# vilnius_rev_c.net
KiCad netlist of a schematic drawn in EAGLE
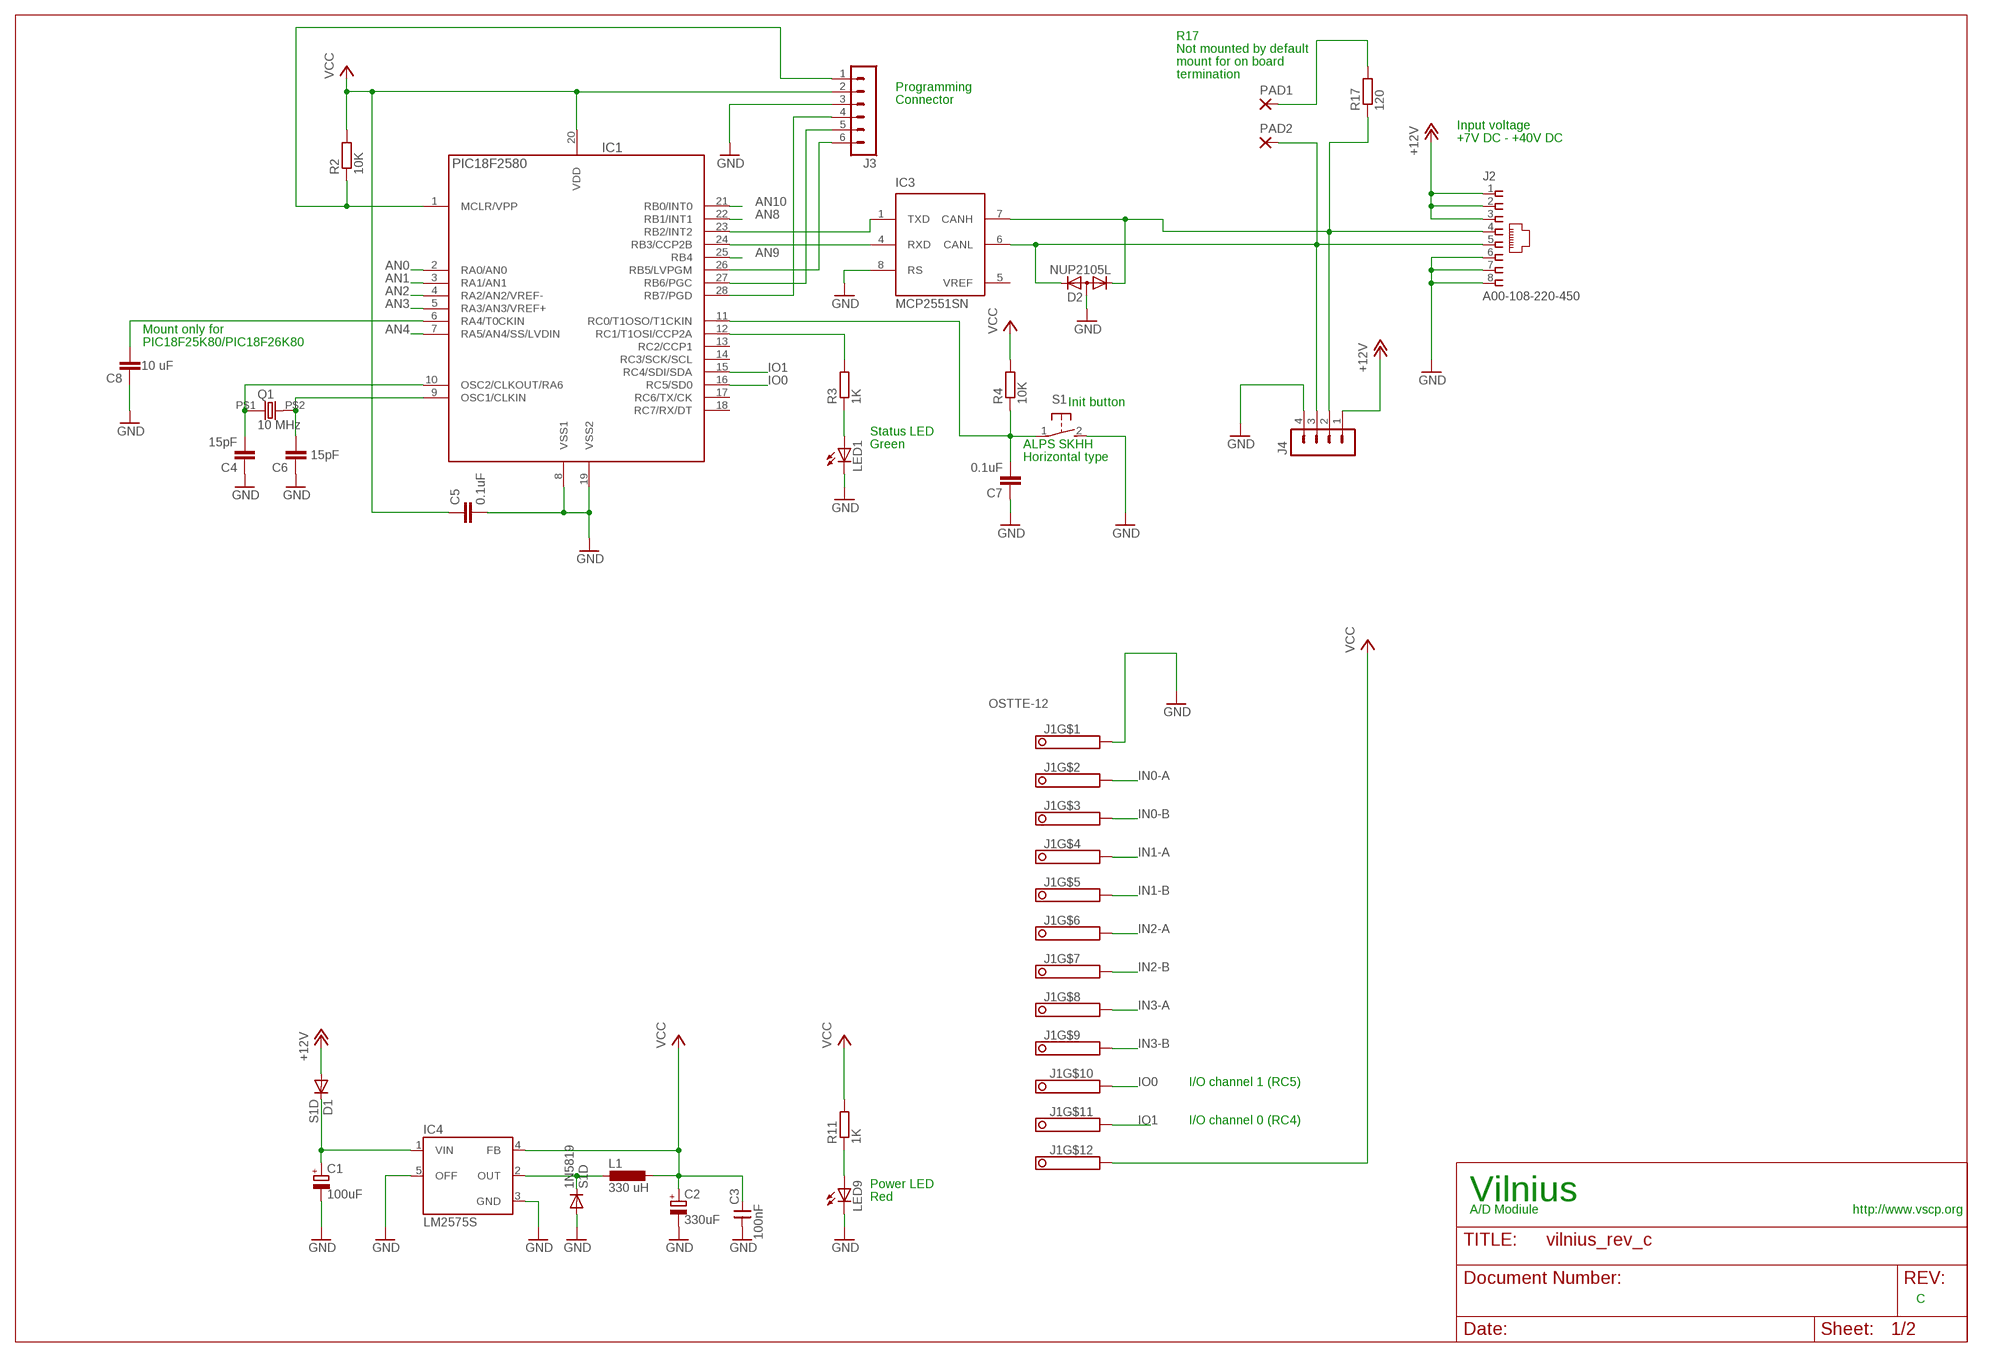
[diagram p0: schematic, sheet 1]
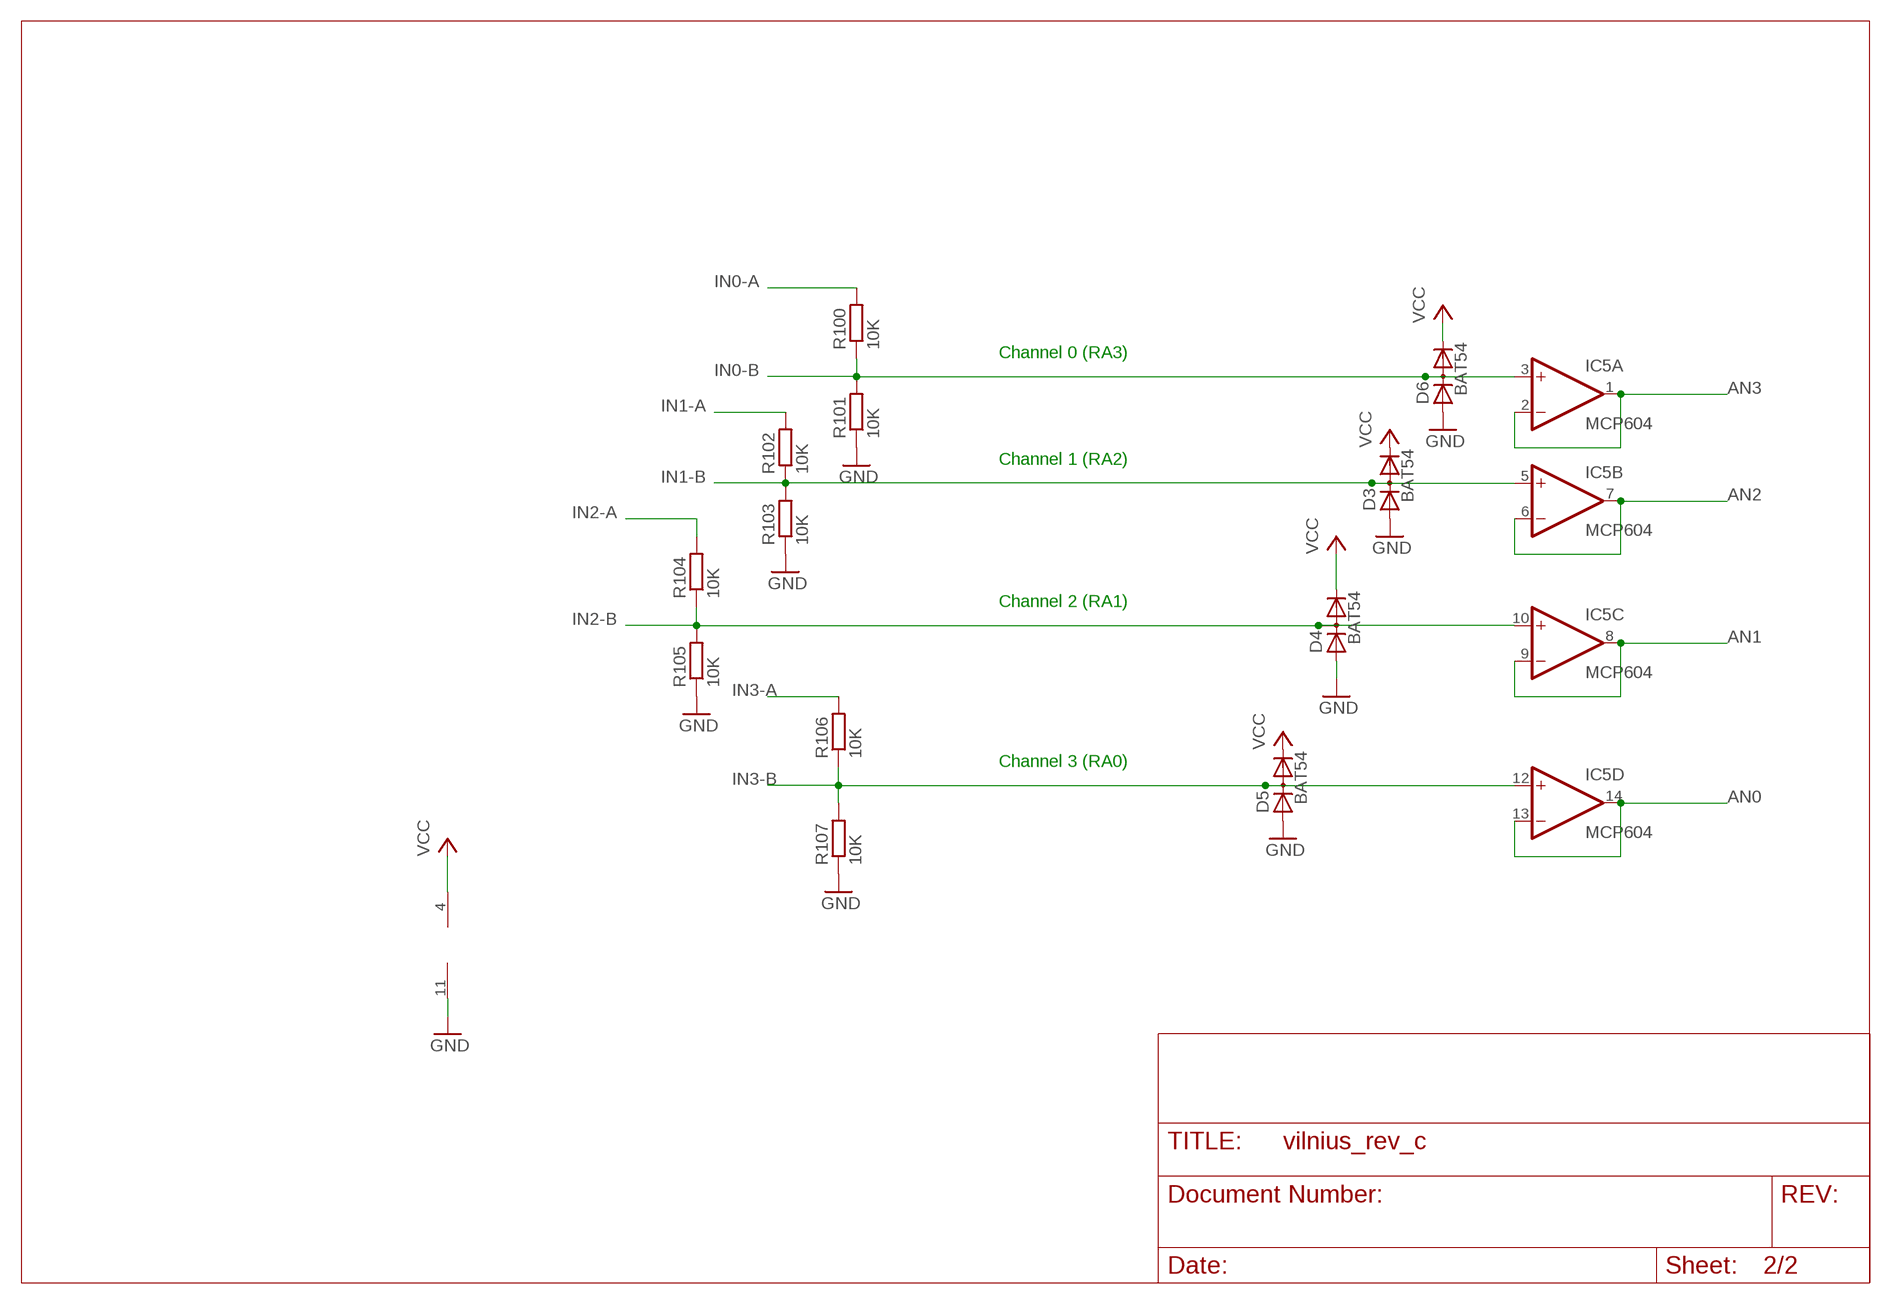
[diagram p1: schematic, sheet 2]

(export (version "E")
  (design (tool "Eeschema 10.0.6"))
  (components
    (comp (ref "1N5819")
      (value "S1D")
      (footprint "eagle-import:SOD123")
      (libsource (lib "eagle-import") (part "DIODE-SOD123"))
    )
    (comp (ref "C1")
      (value "100uF")
      (footprint "eagle-import:PANASONIC_D")
      (libsource (lib "eagle-import") (part "CPOL-EUD"))
    )
    (comp (ref "C2")
      (value "330uF")
      (footprint "eagle-import:PANASONIC_D")
      (libsource (lib "eagle-import") (part "CPOL-EUD"))
    )
    (comp (ref "C3")
      (value "100nF")
      (footprint "eagle-import:0805")
      (libsource (lib "eagle-import") (part "CNP-0805"))
    )
    (comp (ref "C4")
      (value "15pF")
      (footprint "eagle-import:C0805")
      (libsource (lib "eagle-import") (part "C-EUC0805"))
    )
    (comp (ref "C5")
      (value "0.1uF")
      (footprint "eagle-import:C0805")
      (libsource (lib "eagle-import") (part "C-EUC0805"))
    )
    (comp (ref "C6")
      (value "15pF")
      (footprint "eagle-import:C0805")
      (libsource (lib "eagle-import") (part "C-EUC0805"))
    )
    (comp (ref "C7")
      (value "0.1uF")
      (footprint "eagle-import:C0805")
      (libsource (lib "eagle-import") (part "C-EUC0805"))
    )
    (comp (ref "C8")
      (value "10 uF")
      (footprint "eagle-import:C0805")
      (libsource (lib "eagle-import") (part "C-EUC0805"))
    )
    (comp (ref "D1")
      (value "S1D")
      (footprint "eagle-import:SOD123")
      (libsource (lib "eagle-import") (part "DIODE-SOD123"))
    )
    (comp (ref "D2")
      (value "NUP2105L")
      (footprint "eagle-import:SOT23@1")
      (libsource (lib "eagle-import") (part "DIODE-2CA|ACSOT23"))
    )
    (comp (ref "IC1")
      (value "PIC18F2580")
      (footprint "eagle-import:SO28")
      (libsource (lib "eagle-import") (part "PIC18F252-?I/SOL"))
    )
    (comp (ref "IC3")
      (value "MCP2551SN")
      (footprint "eagle-import:SO-08")
      (libsource (lib "eagle-import") (part "MCP2551SN"))
    )
    (comp (ref "IC4")
      (value "LM2575S")
      (footprint "eagle-import:TO263-5")
      (libsource (lib "eagle-import") (part "LM2575S"))
    )
    (comp (ref "J1")
      (value "OSTTE-12")
      (footprint "eagle-import:PINHEAD-12")
      (libsource (lib "eagle-import") (part "OSTTE-12"))
    )
    (comp (ref "J2")
      (value "A00-108-220-450")
      (footprint "eagle-import:RJ-45")
      (libsource (lib "eagle-import") (part "A00-108-220-450"))
    )
    (comp (ref "J3")
      (value "MA06-1")
      (footprint "eagle-import:MA06-1")
      (libsource (lib "eagle-import") (part "MA06-1"))
    )
    (comp (ref "J4")
      (value "MA04-1")
      (footprint "eagle-import:MA04-1")
      (libsource (lib "eagle-import") (part "MA04-1"))
    )
    (comp (ref "L1")
      (value "330 uH")
      (footprint "eagle-import:DO3316P")
      (libsource (lib "eagle-import") (part "DO3316P"))
    )
    (comp (ref "LED1")
      (value "LEDCHIP-LED0805")
      (footprint "eagle-import:CHIP-LED0805")
      (libsource (lib "eagle-import") (part "LEDCHIP-LED0805"))
    )
    (comp (ref "LED9")
      (value "LEDCHIP-LED0805")
      (footprint "eagle-import:CHIP-LED0805")
      (libsource (lib "eagle-import") (part "LEDCHIP-LED0805"))
    )
    (comp (ref "PAD1")
      (value "1,6/0,8")
      (footprint "eagle-import:1,6_0,8")
      (libsource (lib "eagle-import") (part "1,6/0,8"))
    )
    (comp (ref "PAD2")
      (value "1,6/0,8")
      (footprint "eagle-import:1,6_0,8")
      (libsource (lib "eagle-import") (part "1,6/0,8"))
    )
    (comp (ref "Q1")
      (value "10 MHz")
      (footprint "eagle-import:9C")
      (libsource (lib "eagle-import") (part "HC-49S"))
    )
    (comp (ref "R2")
      (value "10K")
      (footprint "eagle-import:R0805")
      (libsource (lib "eagle-import") (part "R-EU_R0805"))
    )
    (comp (ref "R3")
      (value "1K")
      (footprint "eagle-import:R0805")
      (libsource (lib "eagle-import") (part "R-EU_R0805"))
    )
    (comp (ref "R4")
      (value "10K")
      (footprint "eagle-import:R0805")
      (libsource (lib "eagle-import") (part "R-EU_R0805"))
    )
    (comp (ref "R11")
      (value "1K")
      (footprint "eagle-import:R0805")
      (libsource (lib "eagle-import") (part "R-EU_R0805"))
    )
    (comp (ref "R17")
      (value "120")
      (footprint "eagle-import:R0805")
      (libsource (lib "eagle-import") (part "R-EU_R0805"))
    )
    (comp (ref "S1")
      (value "31-XX")
      (footprint "eagle-import:B3F-31XX")
      (fields (field (name "MPN") "B3F-3100"))
      (libsource (lib "eagle-import") (part "31-XX"))
    )
    (comp (ref "D3")
      (value "BAT54")
      (footprint "eagle-import:SOT23")
      (libsource (lib "eagle-import") (part "BAV199"))
    )
    (comp (ref "D4")
      (value "BAT54")
      (footprint "eagle-import:SOT23")
      (libsource (lib "eagle-import") (part "BAV199"))
    )
    (comp (ref "D5")
      (value "BAT54")
      (footprint "eagle-import:SOT23")
      (libsource (lib "eagle-import") (part "BAV199"))
    )
    (comp (ref "D6")
      (value "BAT54")
      (footprint "eagle-import:SOT23")
      (libsource (lib "eagle-import") (part "BAV199"))
    )
    (comp (ref "IC5")
      (value "MCP604")
      (footprint "eagle-import:SO14")
      (libsource (lib "eagle-import") (part "4AMP_P4+11D"))
    )
    (comp (ref "R100")
      (value "10K")
      (footprint "eagle-import:R0805")
      (libsource (lib "eagle-import") (part "R-EU_R0805"))
    )
    (comp (ref "R101")
      (value "10K")
      (footprint "eagle-import:R0805")
      (libsource (lib "eagle-import") (part "R-EU_R0805"))
    )
    (comp (ref "R102")
      (value "10K")
      (footprint "eagle-import:R0805")
      (libsource (lib "eagle-import") (part "R-EU_R0805"))
    )
    (comp (ref "R103")
      (value "10K")
      (footprint "eagle-import:R0805")
      (libsource (lib "eagle-import") (part "R-EU_R0805"))
    )
    (comp (ref "R104")
      (value "10K")
      (footprint "eagle-import:R0805")
      (libsource (lib "eagle-import") (part "R-EU_R0805"))
    )
    (comp (ref "R105")
      (value "10K")
      (footprint "eagle-import:R0805")
      (libsource (lib "eagle-import") (part "R-EU_R0805"))
    )
    (comp (ref "R106")
      (value "10K")
      (footprint "eagle-import:R0805")
      (libsource (lib "eagle-import") (part "R-EU_R0805"))
    )
    (comp (ref "R107")
      (value "10K")
      (footprint "eagle-import:R0805")
      (libsource (lib "eagle-import") (part "R-EU_R0805"))
    )
  )
  (nets
    (net (code "1") (name "+12V") (class "Default")
      (node (ref "D1") (pin "A") (pinfunction "A_A") (pintype "passive"))
      (node (ref "J2") (pin "1") (pinfunction "1_1") (pintype "passive"))
      (node (ref "J2") (pin "2") (pinfunction "2_2") (pintype "passive"))
      (node (ref "J2") (pin "3") (pinfunction "3_3") (pintype "passive"))
      (node (ref "J4") (pin "1") (pinfunction "1_1") (pintype "passive"))
    )
    (net (code "2") (name "AN0") (class "Default")
      (node (ref "IC1") (pin "2") (pinfunction "RA0/AN0_2") (pintype "bidirectional"))
      (node (ref "IC5") (pin "13") (pinfunction "-IN_13") (pintype "input"))
      (node (ref "IC5") (pin "14") (pinfunction "OUT_14") (pintype "output"))
    )
    (net (code "3") (name "AN1") (class "Default")
      (node (ref "IC1") (pin "3") (pinfunction "RA1/AN1_3") (pintype "bidirectional"))
      (node (ref "IC5") (pin "8") (pinfunction "OUT_8") (pintype "output"))
      (node (ref "IC5") (pin "9") (pinfunction "-IN_9") (pintype "input"))
    )
    (net (code "4") (name "AN2") (class "Default")
      (node (ref "IC1") (pin "4") (pinfunction "RA2/AN2/VREF-_4") (pintype "bidirectional"))
      (node (ref "IC5") (pin "6") (pinfunction "-IN_6") (pintype "input"))
      (node (ref "IC5") (pin "7") (pinfunction "OUT_7") (pintype "output"))
    )
    (net (code "5") (name "AN3") (class "Default")
      (node (ref "IC1") (pin "5") (pinfunction "RA3/AN3/VREF+_5") (pintype "bidirectional"))
      (node (ref "IC5") (pin "1") (pinfunction "OUT_1") (pintype "output"))
      (node (ref "IC5") (pin "2") (pinfunction "-IN_2") (pintype "input"))
    )
    (net (code "6") (name "AN4") (class "Default")
      (node (ref "IC1") (pin "7") (pinfunction "RA5/AN4/SS/LVDIN_7") (pintype "bidirectional"))
    )
    (net (code "7") (name "AN8") (class "Default")
      (node (ref "IC1") (pin "22") (pinfunction "RB1/INT1_22") (pintype "bidirectional"))
    )
    (net (code "8") (name "AN9") (class "Default")
      (node (ref "IC1") (pin "25") (pinfunction "RB4_25") (pintype "bidirectional"))
    )
    (net (code "9") (name "AN10") (class "Default")
      (node (ref "IC1") (pin "21") (pinfunction "RB0/INT0_21") (pintype "bidirectional"))
    )
    (net (code "10") (name "GND") (class "Default")
      (node (ref "1N5819") (pin "A") (pinfunction "A_A") (pintype "passive"))
      (node (ref "C1") (pin "-") (pinfunction "-_-") (pintype "passive"))
      (node (ref "C2") (pin "-") (pinfunction "-_-") (pintype "passive"))
      (node (ref "C3") (pin "1") (pinfunction "1_1") (pintype "passive"))
      (node (ref "C4") (pin "1") (pinfunction "1_1") (pintype "passive"))
      (node (ref "C5") (pin "2") (pinfunction "2_2") (pintype "passive"))
      (node (ref "C6") (pin "1") (pinfunction "1_1") (pintype "passive"))
      (node (ref "C7") (pin "1") (pinfunction "1_1") (pintype "passive"))
      (node (ref "C8") (pin "1") (pinfunction "1_1") (pintype "passive"))
      (node (ref "D2") (pin "3") (pinfunction "A_3") (pintype "passive"))
      (node (ref "D3") (pin "1") (pinfunction "A_1") (pintype "passive"))
      (node (ref "D4") (pin "1") (pinfunction "A_1") (pintype "passive"))
      (node (ref "D5") (pin "1") (pinfunction "A_1") (pintype "passive"))
      (node (ref "D6") (pin "1") (pinfunction "A_1") (pintype "passive"))
      (node (ref "IC1") (pin "19") (pinfunction "VSS2_19") (pintype "power_in"))
      (node (ref "IC1") (pin "8") (pinfunction "VSS1_8") (pintype "power_in"))
      (node (ref "IC3") (pin "8") (pinfunction "RS_8") (pintype "input"))
      (node (ref "IC4") (pin "3") (pinfunction "GND_3") (pintype "power_in"))
      (node (ref "IC4") (pin "5") (pinfunction "OFF_5") (pintype "input"))
      (node (ref "IC5") (pin "11") (pinfunction "V-_11") (pintype "power_in"))
      (node (ref "J1") (pin "1") (pinfunction "K_1") (pintype "passive"))
      (node (ref "J2") (pin "6") (pinfunction "6_6") (pintype "passive"))
      (node (ref "J2") (pin "7") (pinfunction "7_7") (pintype "passive"))
      (node (ref "J2") (pin "8") (pinfunction "8_8") (pintype "passive"))
      (node (ref "J3") (pin "3") (pinfunction "3_3") (pintype "passive"))
      (node (ref "J4") (pin "4") (pinfunction "4_4") (pintype "passive"))
      (node (ref "LED1") (pin "C") (pinfunction "C_C") (pintype "passive"))
      (node (ref "LED9") (pin "C") (pinfunction "C_C") (pintype "passive"))
      (node (ref "R101") (pin "1") (pinfunction "1_1") (pintype "passive"))
      (node (ref "R103") (pin "1") (pinfunction "1_1") (pintype "passive"))
      (node (ref "R105") (pin "1") (pinfunction "1_1") (pintype "passive"))
      (node (ref "R107") (pin "1") (pinfunction "1_1") (pintype "passive"))
      (node (ref "S1") (pin "2") (pinfunction "S_2") (pintype "passive"))
    )
    (net (code "11") (name "IN0-A") (class "Default")
      (node (ref "J1") (pin "2") (pinfunction "K_2") (pintype "passive"))
      (node (ref "R100") (pin "2") (pinfunction "2_2") (pintype "passive"))
    )
    (net (code "12") (name "IN0-B") (class "Default")
      (node (ref "D6") (pin "3") (pinfunction "AC_3") (pintype "passive"))
      (node (ref "IC5") (pin "3") (pinfunction "+IN_3") (pintype "input"))
      (node (ref "J1") (pin "3") (pinfunction "K_3") (pintype "passive"))
      (node (ref "R100") (pin "1") (pinfunction "1_1") (pintype "passive"))
      (node (ref "R101") (pin "2") (pinfunction "2_2") (pintype "passive"))
    )
    (net (code "13") (name "IN1-A") (class "Default")
      (node (ref "J1") (pin "4") (pinfunction "K_4") (pintype "passive"))
      (node (ref "R102") (pin "2") (pinfunction "2_2") (pintype "passive"))
    )
    (net (code "14") (name "IN1-B") (class "Default")
      (node (ref "D3") (pin "3") (pinfunction "AC_3") (pintype "passive"))
      (node (ref "IC5") (pin "5") (pinfunction "+IN_5") (pintype "input"))
      (node (ref "J1") (pin "5") (pinfunction "K_5") (pintype "passive"))
      (node (ref "R102") (pin "1") (pinfunction "1_1") (pintype "passive"))
      (node (ref "R103") (pin "2") (pinfunction "2_2") (pintype "passive"))
    )
    (net (code "15") (name "IN2-A") (class "Default")
      (node (ref "J1") (pin "6") (pinfunction "K_6") (pintype "passive"))
      (node (ref "R104") (pin "2") (pinfunction "2_2") (pintype "passive"))
    )
    (net (code "16") (name "IN2-B") (class "Default")
      (node (ref "D4") (pin "3") (pinfunction "AC_3") (pintype "passive"))
      (node (ref "IC5") (pin "10") (pinfunction "+IN_10") (pintype "input"))
      (node (ref "J1") (pin "7") (pinfunction "K_7") (pintype "passive"))
      (node (ref "R104") (pin "1") (pinfunction "1_1") (pintype "passive"))
      (node (ref "R105") (pin "2") (pinfunction "2_2") (pintype "passive"))
    )
    (net (code "17") (name "IN3-A") (class "Default")
      (node (ref "J1") (pin "8") (pinfunction "K_8") (pintype "passive"))
      (node (ref "R106") (pin "2") (pinfunction "2_2") (pintype "passive"))
    )
    (net (code "18") (name "IN3-B") (class "Default")
      (node (ref "D5") (pin "3") (pinfunction "AC_3") (pintype "passive"))
      (node (ref "IC5") (pin "12") (pinfunction "+IN_12") (pintype "input"))
      (node (ref "J1") (pin "9") (pinfunction "K_9") (pintype "passive"))
      (node (ref "R106") (pin "1") (pinfunction "1_1") (pintype "passive"))
      (node (ref "R107") (pin "2") (pinfunction "2_2") (pintype "passive"))
    )
    (net (code "19") (name "IO0") (class "Default")
      (node (ref "IC1") (pin "16") (pinfunction "RC5/SD0_16") (pintype "bidirectional"))
      (node (ref "J1") (pin "10") (pinfunction "K_10") (pintype "passive"))
    )
    (net (code "20") (name "IO1") (class "Default")
      (node (ref "IC1") (pin "15") (pinfunction "RC4/SDI/SDA_15") (pintype "bidirectional"))
      (node (ref "J1") (pin "11") (pinfunction "K_11") (pintype "passive"))
    )
    (net (code "21") (name "Net-(D2-K1)") (class "Default")
      (node (ref "D2") (pin "1") (pinfunction "K1_1") (pintype "passive"))
      (node (ref "IC3") (pin "7") (pinfunction "CANH_7") (pintype "bidirectional"))
      (node (ref "J2") (pin "4") (pinfunction "4_4") (pintype "passive"))
      (node (ref "J4") (pin "2") (pinfunction "2_2") (pintype "passive"))
      (node (ref "R17") (pin "1") (pinfunction "1_1") (pintype "passive"))
    )
    (net (code "22") (name "Net-(D2-K2)") (class "Default")
      (node (ref "D2") (pin "2") (pinfunction "K2_2") (pintype "passive"))
      (node (ref "IC3") (pin "6") (pinfunction "CANL_6") (pintype "bidirectional"))
      (node (ref "J2") (pin "5") (pinfunction "5_5") (pintype "passive"))
      (node (ref "J4") (pin "3") (pinfunction "3_3") (pintype "passive"))
      (node (ref "PAD2") (pin "1") (pinfunction "P_1") (pintype "passive"))
    )
    (net (code "23") (name "Net-(IC1-MCLR{slash}VPP)") (class "Default")
      (node (ref "IC1") (pin "1") (pinfunction "MCLR/VPP_1") (pintype "input"))
      (node (ref "J3") (pin "1") (pinfunction "1_1") (pintype "passive"))
      (node (ref "R2") (pin "1") (pinfunction "1_1") (pintype "passive"))
    )
    (net (code "24") (name "Net-(IC1-OSC1{slash}CLKIN)") (class "Default")
      (node (ref "C6") (pin "2") (pinfunction "2_2") (pintype "passive"))
      (node (ref "IC1") (pin "9") (pinfunction "OSC1/CLKIN_9") (pintype "input"))
      (node (ref "Q1") (pin "P$2") (pinfunction "2_P$2") (pintype "passive"))
    )
    (net (code "25") (name "Net-(IC1-OSC2{slash}CLKOUT{slash}RA6)") (class "Default")
      (node (ref "C4") (pin "2") (pinfunction "2_2") (pintype "passive"))
      (node (ref "IC1") (pin "10") (pinfunction "OSC2/CLKOUT/RA6_10") (pintype "output"))
      (node (ref "Q1") (pin "P$1") (pinfunction "1_P$1") (pintype "passive"))
    )
    (net (code "26") (name "Net-(IC1-RA4{slash}T0CKIN)") (class "Default")
      (node (ref "C8") (pin "2") (pinfunction "2_2") (pintype "passive"))
      (node (ref "IC1") (pin "6") (pinfunction "RA4/T0CKIN_6") (pintype "open_collector"))
    )
    (net (code "27") (name "Net-(IC1-RB2{slash}INT2)") (class "Default")
      (node (ref "IC1") (pin "23") (pinfunction "RB2/INT2_23") (pintype "bidirectional"))
      (node (ref "IC3") (pin "1") (pinfunction "TXD_1") (pintype "input"))
    )
    (net (code "28") (name "Net-(IC1-RB3{slash}CCP2B)") (class "Default")
      (node (ref "IC1") (pin "24") (pinfunction "RB3/CCP2B_24") (pintype "bidirectional"))
      (node (ref "IC3") (pin "4") (pinfunction "RXD_4") (pintype "output"))
    )
    (net (code "29") (name "Net-(IC1-RB5{slash}LVPGM)") (class "Default")
      (node (ref "IC1") (pin "26") (pinfunction "RB5/LVPGM_26") (pintype "bidirectional"))
      (node (ref "J3") (pin "6") (pinfunction "6_6") (pintype "passive"))
    )
    (net (code "30") (name "Net-(IC1-RB6{slash}PGC)") (class "Default")
      (node (ref "IC1") (pin "27") (pinfunction "RB6/PGC_27") (pintype "bidirectional"))
      (node (ref "J3") (pin "5") (pinfunction "5_5") (pintype "passive"))
    )
    (net (code "31") (name "Net-(IC1-RB7{slash}PGD)") (class "Default")
      (node (ref "IC1") (pin "28") (pinfunction "RB7/PGD_28") (pintype "bidirectional"))
      (node (ref "J3") (pin "4") (pinfunction "4_4") (pintype "passive"))
    )
    (net (code "32") (name "Net-(IC1-RC0{slash}T1OSO{slash}T1CKIN)") (class "Default")
      (node (ref "C7") (pin "2") (pinfunction "2_2") (pintype "passive"))
      (node (ref "IC1") (pin "11") (pinfunction "RC0/T1OSO/T1CKIN_11") (pintype "bidirectional"))
      (node (ref "R4") (pin "1") (pinfunction "1_1") (pintype "passive"))
      (node (ref "S1") (pin "1") (pinfunction "P_1") (pintype "passive"))
    )
    (net (code "33") (name "Net-(IC1-RC1{slash}T1OSI{slash}CCP2A)") (class "Default")
      (node (ref "IC1") (pin "12") (pinfunction "RC1/T1OSI/CCP2A_12") (pintype "bidirectional"))
      (node (ref "R3") (pin "2") (pinfunction "2_2") (pintype "passive"))
    )
    (net (code "34") (name "Net-(IC4-OUT)") (class "Default")
      (node (ref "1N5819") (pin "C") (pinfunction "C_C") (pintype "passive"))
      (node (ref "IC4") (pin "2") (pinfunction "OUT_2") (pintype "output"))
      (node (ref "L1") (pin "1") (pinfunction "1_1") (pintype "passive"))
    )
    (net (code "35") (name "Net-(IC4-VIN)") (class "Default")
      (node (ref "C1") (pin "+") (pinfunction "+_+") (pintype "passive"))
      (node (ref "D1") (pin "C") (pinfunction "C_C") (pintype "passive"))
      (node (ref "IC4") (pin "1") (pinfunction "VIN_1") (pintype "power_in"))
    )
    (net (code "36") (name "Net-(LED1-PadA)") (class "Default")
      (node (ref "LED1") (pin "A") (pinfunction "A_A") (pintype "passive"))
      (node (ref "R3") (pin "1") (pinfunction "1_1") (pintype "passive"))
    )
    (net (code "37") (name "Net-(LED9-PadA)") (class "Default")
      (node (ref "LED9") (pin "A") (pinfunction "A_A") (pintype "passive"))
      (node (ref "R11") (pin "1") (pinfunction "1_1") (pintype "passive"))
    )
    (net (code "38") (name "Net-(PAD1-P)") (class "Default")
      (node (ref "PAD1") (pin "1") (pinfunction "P_1") (pintype "passive"))
      (node (ref "R17") (pin "2") (pinfunction "2_2") (pintype "passive"))
    )
    (net (code "39") (name "VCC") (class "Default")
      (node (ref "C2") (pin "+") (pinfunction "+_+") (pintype "passive"))
      (node (ref "C3") (pin "2") (pinfunction "2_2") (pintype "passive"))
      (node (ref "C5") (pin "1") (pinfunction "1_1") (pintype "passive"))
      (node (ref "D3") (pin "2") (pinfunction "C_2") (pintype "passive"))
      (node (ref "D4") (pin "2") (pinfunction "C_2") (pintype "passive"))
      (node (ref "D5") (pin "2") (pinfunction "C_2") (pintype "passive"))
      (node (ref "D6") (pin "2") (pinfunction "C_2") (pintype "passive"))
      (node (ref "IC1") (pin "20") (pinfunction "VDD_20") (pintype "power_in"))
      (node (ref "IC4") (pin "4") (pinfunction "FB_4") (pintype "input"))
      (node (ref "IC5") (pin "4") (pinfunction "V+_4") (pintype "power_in"))
      (node (ref "J1") (pin "12") (pinfunction "K_12") (pintype "passive"))
      (node (ref "J3") (pin "2") (pinfunction "2_2") (pintype "passive"))
      (node (ref "L1") (pin "2") (pinfunction "2_2") (pintype "passive"))
      (node (ref "R11") (pin "2") (pinfunction "2_2") (pintype "passive"))
      (node (ref "R2") (pin "2") (pinfunction "2_2") (pintype "passive"))
      (node (ref "R4") (pin "2") (pinfunction "2_2") (pintype "passive"))
    )
    (net (code "40") (name "VREF") (class "Default")
      (node (ref "IC3") (pin "5") (pinfunction "VREF_5") (pintype "power_in"))
    )
    (net (code "41") (name "unconnected-(IC1-RC2{slash}CCP1-Pad13)") (class "Default")
      (node (ref "IC1") (pin "13") (pinfunction "RC2/CCP1_13") (pintype "bidirectional"))
    )
    (net (code "42") (name "unconnected-(IC1-RC3{slash}SCK{slash}SCL-Pad14)") (class "Default")
      (node (ref "IC1") (pin "14") (pinfunction "RC3/SCK/SCL_14") (pintype "bidirectional"))
    )
    (net (code "43") (name "unconnected-(IC1-RC6{slash}TX{slash}CK-Pad17)") (class "Default")
      (node (ref "IC1") (pin "17") (pinfunction "RC6/TX/CK_17") (pintype "bidirectional"))
    )
    (net (code "44") (name "unconnected-(IC1-RC7{slash}RX{slash}DT-Pad18)") (class "Default")
      (node (ref "IC1") (pin "18") (pinfunction "RC7/RX/DT_18") (pintype "bidirectional"))
    )
  )
)
